# HOTAS_THUMB_v5_brd.net
KiCad netlist of a schematic drawn in EAGLE
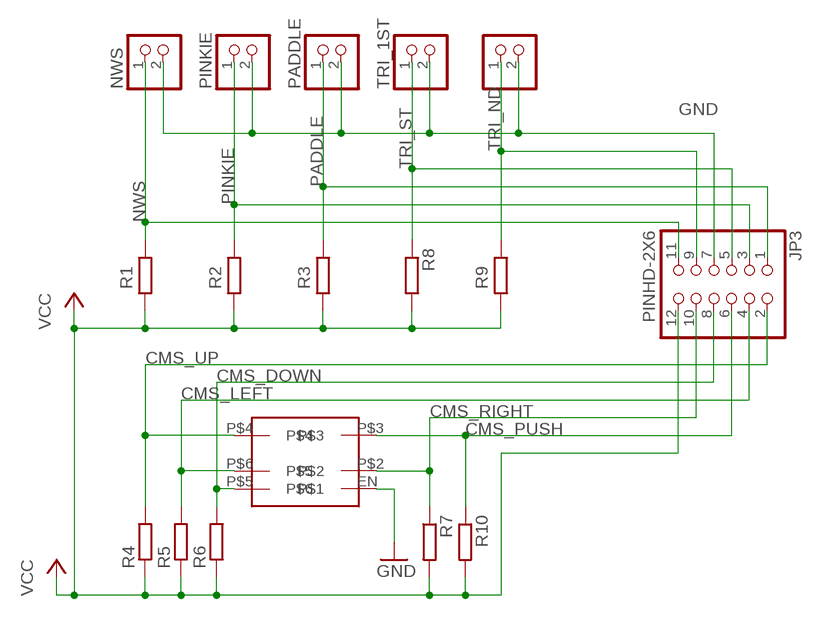
[diagram p0: schematic, sheet 1]

(export (version "E")
  (design (tool "Eeschema 10.0.6"))
  (components
    (comp (ref "JP3")
      (value "PINHD-2X6")
      (footprint "eagle-import:2X06")
      (fields (field (name "MANUFACTURER") "Generic"))
      (libsource (lib "eagle-import") (part "PINHD-2X6"))
    )
    (comp (ref "NWS")
      (value "PINHD-1X2")
      (footprint "eagle-import:1X02")
      (libsource (lib "eagle-import") (part "PINHD-1X2"))
    )
    (comp (ref "PADDLE")
      (value "PINHD-1X2")
      (footprint "eagle-import:1X02")
      (libsource (lib "eagle-import") (part "PINHD-1X2"))
    )
    (comp (ref "PINKIE")
      (value "PINHD-1X2")
      (footprint "eagle-import:1X02")
      (libsource (lib "eagle-import") (part "PINHD-1X2"))
    )
    (comp (ref "R1")
      (value "R_CHIP-1206(3216-METRIC)")
      (footprint "eagle-import:RESC3216X70")
      (libsource (lib "eagle-import") (part "RCHIP-1206(3216-METRIC)_"))
    )
    (comp (ref "R2")
      (value "R_CHIP-1206(3216-METRIC)")
      (footprint "eagle-import:RESC3216X70")
      (libsource (lib "eagle-import") (part "RCHIP-1206(3216-METRIC)_"))
    )
    (comp (ref "R3")
      (value "R_CHIP-1206(3216-METRIC)")
      (footprint "eagle-import:RESC3216X70")
      (libsource (lib "eagle-import") (part "RCHIP-1206(3216-METRIC)_"))
    )
    (comp (ref "R4")
      (value "R_CHIP-1206(3216-METRIC)")
      (footprint "eagle-import:RESC3216X70")
      (libsource (lib "eagle-import") (part "RCHIP-1206(3216-METRIC)_"))
    )
    (comp (ref "R5")
      (value "R_CHIP-1206(3216-METRIC)")
      (footprint "eagle-import:RESC3216X70")
      (libsource (lib "eagle-import") (part "RCHIP-1206(3216-METRIC)_"))
    )
    (comp (ref "R6")
      (value "R_CHIP-1206(3216-METRIC)")
      (footprint "eagle-import:RESC3216X70")
      (libsource (lib "eagle-import") (part "RCHIP-1206(3216-METRIC)_"))
    )
    (comp (ref "R7")
      (value "R_CHIP-1206(3216-METRIC)")
      (footprint "eagle-import:RESC3216X70")
      (libsource (lib "eagle-import") (part "RCHIP-1206(3216-METRIC)_"))
    )
    (comp (ref "R8")
      (value "R_CHIP-1206(3216-METRIC)")
      (footprint "eagle-import:RESC3216X70")
      (libsource (lib "eagle-import") (part "RCHIP-1206(3216-METRIC)_"))
    )
    (comp (ref "R9")
      (value "R_CHIP-1206(3216-METRIC)")
      (footprint "eagle-import:RESC3216X70")
      (libsource (lib "eagle-import") (part "RCHIP-1206(3216-METRIC)_"))
    )
    (comp (ref "R10")
      (value "R_CHIP-1206(3216-METRIC)")
      (footprint "eagle-import:RESC3216X70")
      (libsource (lib "eagle-import") (part "RCHIP-1206(3216-METRIC)_"))
    )
    (comp (ref "TRI_1ST")
      (value "PINHD-1X2")
      (footprint "eagle-import:1X02")
      (libsource (lib "eagle-import") (part "PINHD-1X2"))
    )
    (comp (ref "TRI_ND")
      (value "PINHD-1X2")
      (footprint "eagle-import:1X02")
      (libsource (lib "eagle-import") (part "PINHD-1X2"))
    )
    (comp (ref "U$1")
      (value "FIVEWAYHATSSMD")
      (footprint "eagle-import:FIVEWAYHATSSMD")
      (libsource (lib "eagle-import") (part "FIVEWAYHATSSMD"))
    )
  )
  (nets
    (net (code "1") (name "/CMS_DOWN") (class "Default")
      (node (ref "JP3") (pin "8") (pinfunction "8_8") (pintype "passive"))
      (node (ref "R6") (pin "2") (pinfunction "2_2") (pintype "passive"))
      (node (ref "U$1") (pin "P$5") (pinfunction "P$6_P$5") (pintype "bidirectional"))
    )
    (net (code "2") (name "/CMS_LEFT") (class "Default")
      (node (ref "JP3") (pin "4") (pinfunction "4_4") (pintype "passive"))
      (node (ref "R5") (pin "2") (pinfunction "2_2") (pintype "passive"))
      (node (ref "U$1") (pin "P$6") (pinfunction "P$5_P$6") (pintype "bidirectional"))
    )
    (net (code "3") (name "/CMS_PUSH") (class "Default")
      (node (ref "JP3") (pin "6") (pinfunction "6_6") (pintype "passive"))
      (node (ref "R10") (pin "1") (pinfunction "1_1") (pintype "passive"))
      (node (ref "U$1") (pin "P$3") (pinfunction "P$3_P$3") (pintype "bidirectional"))
    )
    (net (code "4") (name "/CMS_RIGHT") (class "Default")
      (node (ref "JP3") (pin "10") (pinfunction "10_10") (pintype "passive"))
      (node (ref "R7") (pin "1") (pinfunction "1_1") (pintype "passive"))
      (node (ref "U$1") (pin "P$2") (pinfunction "P$2_P$2") (pintype "bidirectional"))
    )
    (net (code "5") (name "/CMS_UP") (class "Default")
      (node (ref "JP3") (pin "2") (pinfunction "2_2") (pintype "passive"))
      (node (ref "R4") (pin "2") (pinfunction "2_2") (pintype "passive"))
      (node (ref "U$1") (pin "P$4") (pinfunction "P$4_P$4") (pintype "bidirectional"))
    )
    (net (code "6") (name "/NWS") (class "Default")
      (node (ref "JP3") (pin "11") (pinfunction "11_11") (pintype "passive"))
      (node (ref "NWS") (pin "1") (pinfunction "1_1") (pintype "passive"))
      (node (ref "R1") (pin "1") (pinfunction "1_1") (pintype "passive"))
    )
    (net (code "7") (name "/PADDLE") (class "Default")
      (node (ref "JP3") (pin "1") (pinfunction "1_1") (pintype "passive"))
      (node (ref "PADDLE") (pin "1") (pinfunction "1_1") (pintype "passive"))
      (node (ref "R3") (pin "1") (pinfunction "1_1") (pintype "passive"))
    )
    (net (code "8") (name "/PINKIE") (class "Default")
      (node (ref "JP3") (pin "3") (pinfunction "3_3") (pintype "passive"))
      (node (ref "PINKIE") (pin "1") (pinfunction "1_1") (pintype "passive"))
      (node (ref "R2") (pin "1") (pinfunction "1_1") (pintype "passive"))
    )
    (net (code "9") (name "/TRI_ND") (class "Default")
      (node (ref "JP3") (pin "9") (pinfunction "9_9") (pintype "passive"))
      (node (ref "R9") (pin "1") (pinfunction "1_1") (pintype "passive"))
      (node (ref "TRI_ND") (pin "1") (pinfunction "1_1") (pintype "passive"))
    )
    (net (code "10") (name "/TRI_ST") (class "Default")
      (node (ref "JP3") (pin "5") (pinfunction "5_5") (pintype "passive"))
      (node (ref "R8") (pin "1") (pinfunction "1_1") (pintype "passive"))
      (node (ref "TRI_1ST") (pin "1") (pinfunction "1_1") (pintype "passive"))
    )
    (net (code "11") (name "GND") (class "Default")
      (node (ref "JP3") (pin "7") (pinfunction "7_7") (pintype "passive"))
      (node (ref "NWS") (pin "2") (pinfunction "2_2") (pintype "passive"))
      (node (ref "PADDLE") (pin "2") (pinfunction "2_2") (pintype "passive"))
      (node (ref "PINKIE") (pin "2") (pinfunction "2_2") (pintype "passive"))
      (node (ref "TRI_1ST") (pin "2") (pinfunction "2_2") (pintype "passive"))
      (node (ref "TRI_ND") (pin "2") (pinfunction "2_2") (pintype "passive"))
      (node (ref "U$1") (pin "EN") (pinfunction "P$1_EN") (pintype "bidirectional"))
    )
    (net (code "12") (name "VCC") (class "Default")
      (node (ref "JP3") (pin "12") (pinfunction "12_12") (pintype "passive"))
      (node (ref "R1") (pin "2") (pinfunction "2_2") (pintype "passive"))
      (node (ref "R10") (pin "2") (pinfunction "2_2") (pintype "passive"))
      (node (ref "R2") (pin "2") (pinfunction "2_2") (pintype "passive"))
      (node (ref "R3") (pin "2") (pinfunction "2_2") (pintype "passive"))
      (node (ref "R4") (pin "1") (pinfunction "1_1") (pintype "passive"))
      (node (ref "R5") (pin "1") (pinfunction "1_1") (pintype "passive"))
      (node (ref "R6") (pin "1") (pinfunction "1_1") (pintype "passive"))
      (node (ref "R7") (pin "2") (pinfunction "2_2") (pintype "passive"))
      (node (ref "R8") (pin "2") (pinfunction "2_2") (pintype "passive"))
      (node (ref "R9") (pin "2") (pinfunction "2_2") (pintype "passive"))
    )
  )
)
